# CARA_brain_v1_2.net
KiCad netlist of a schematic drawn in EAGLE
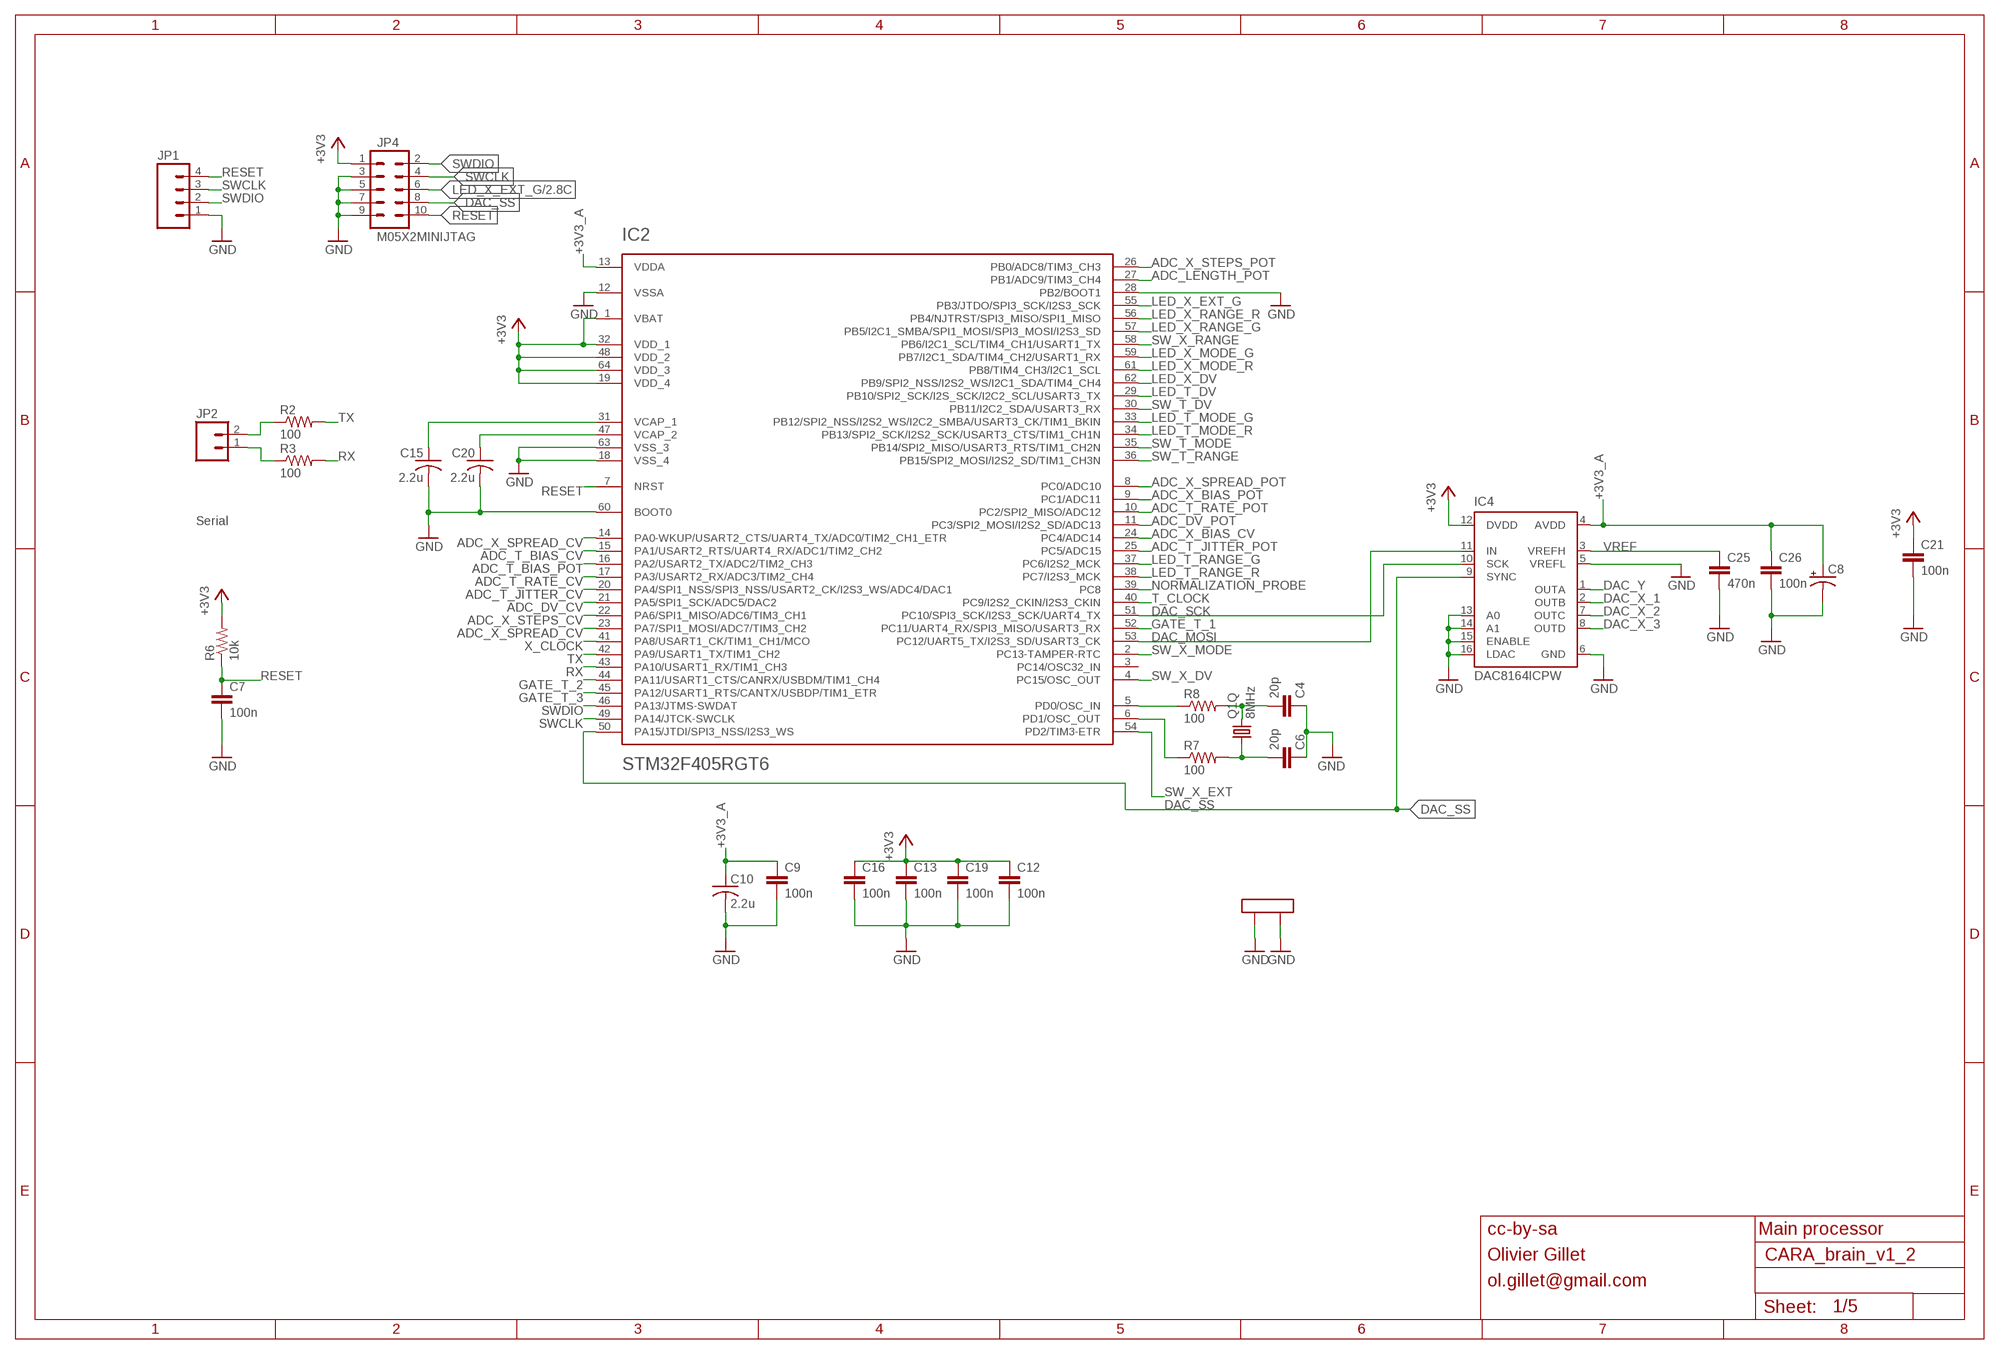
[diagram p0: schematic, sheet 1]
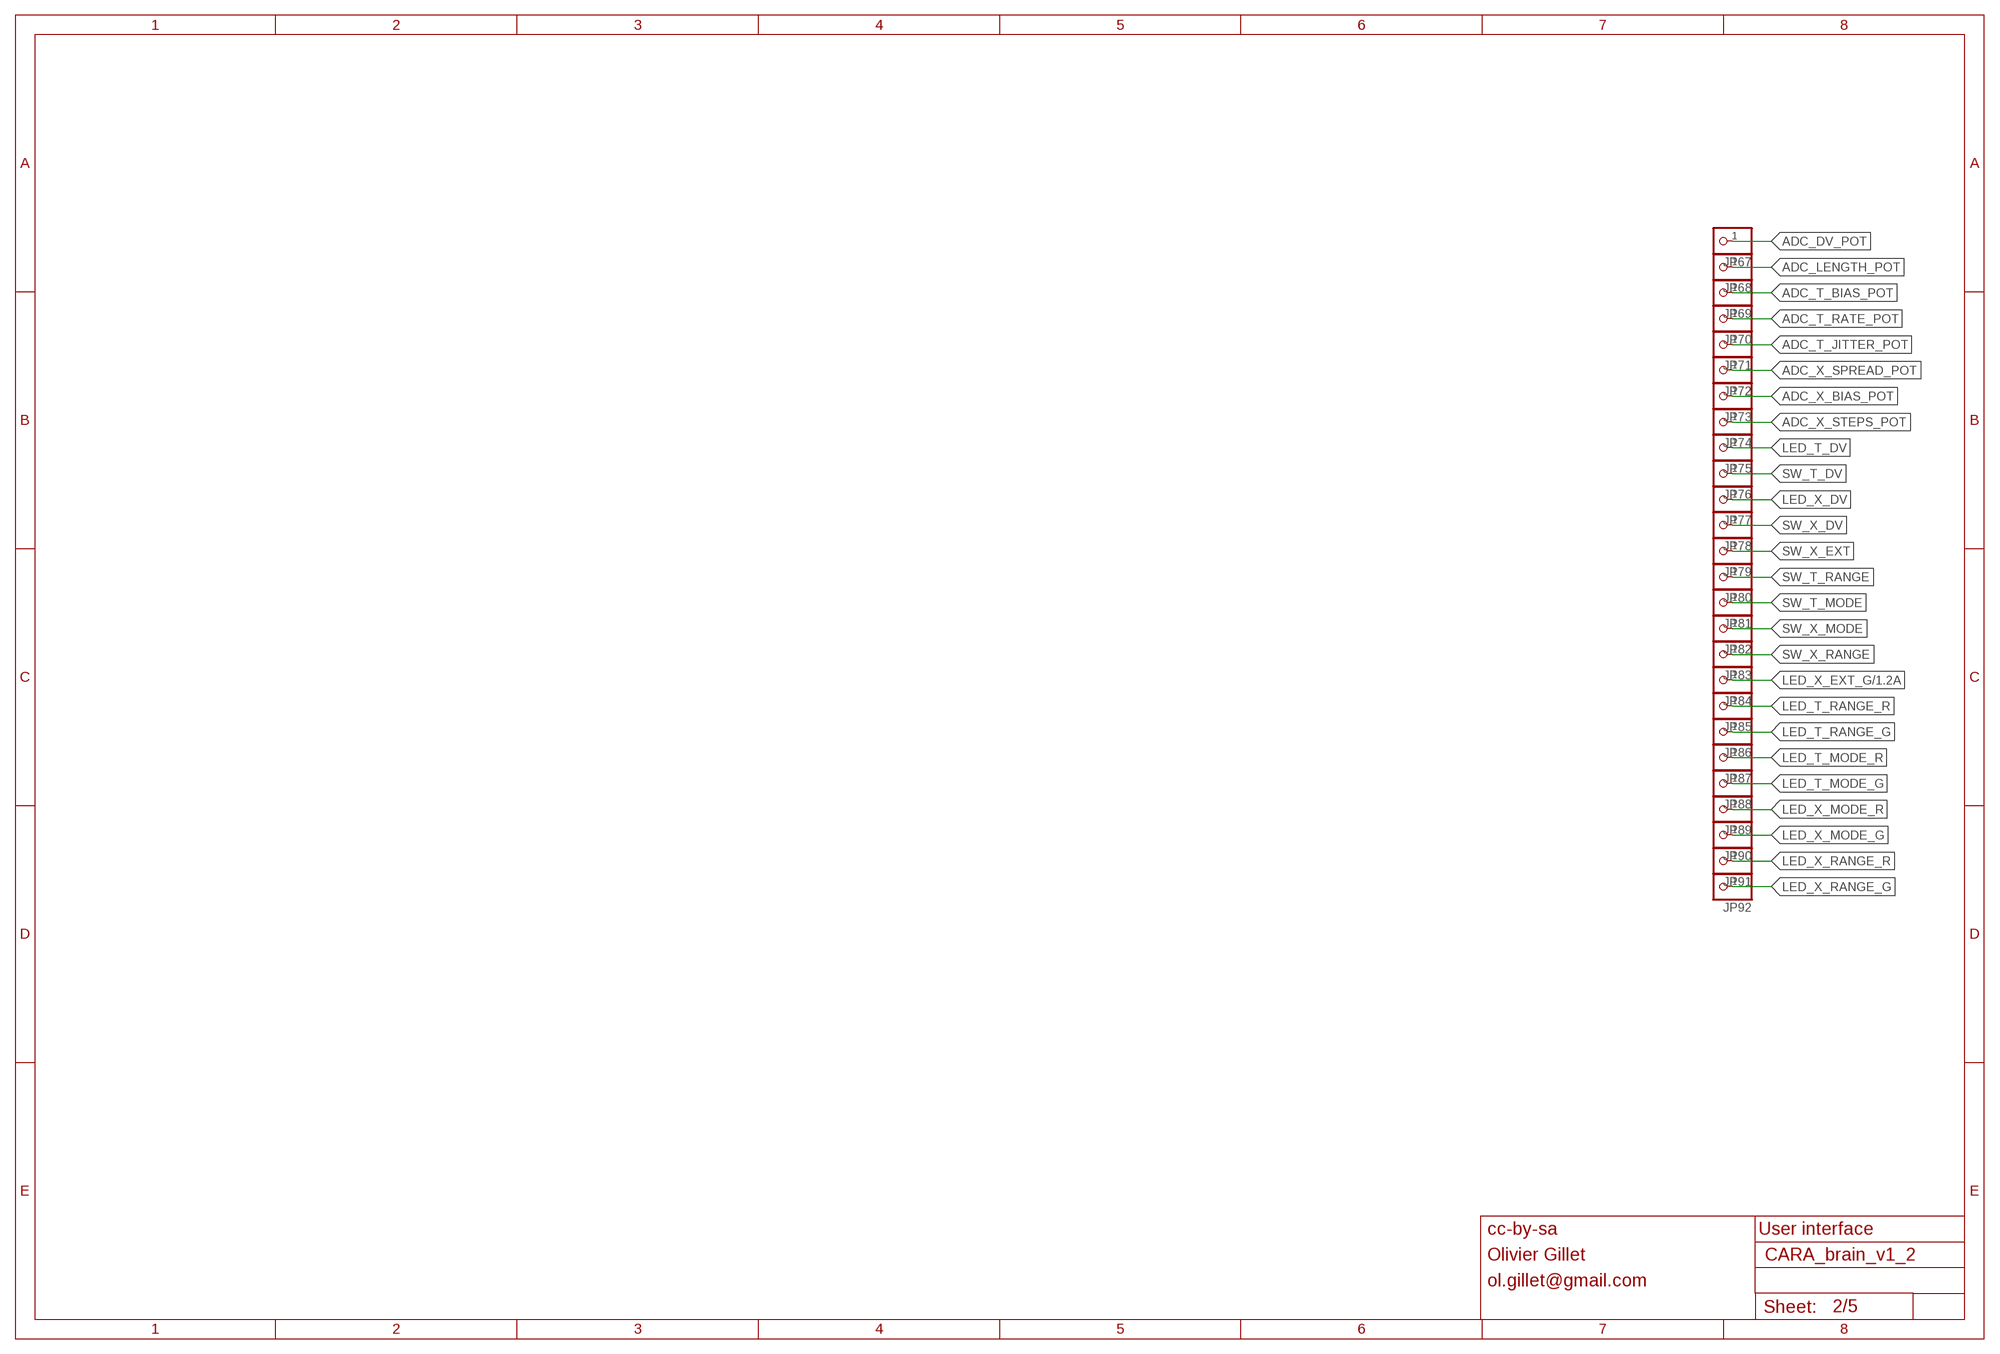
[diagram p1: schematic, sheet 2]
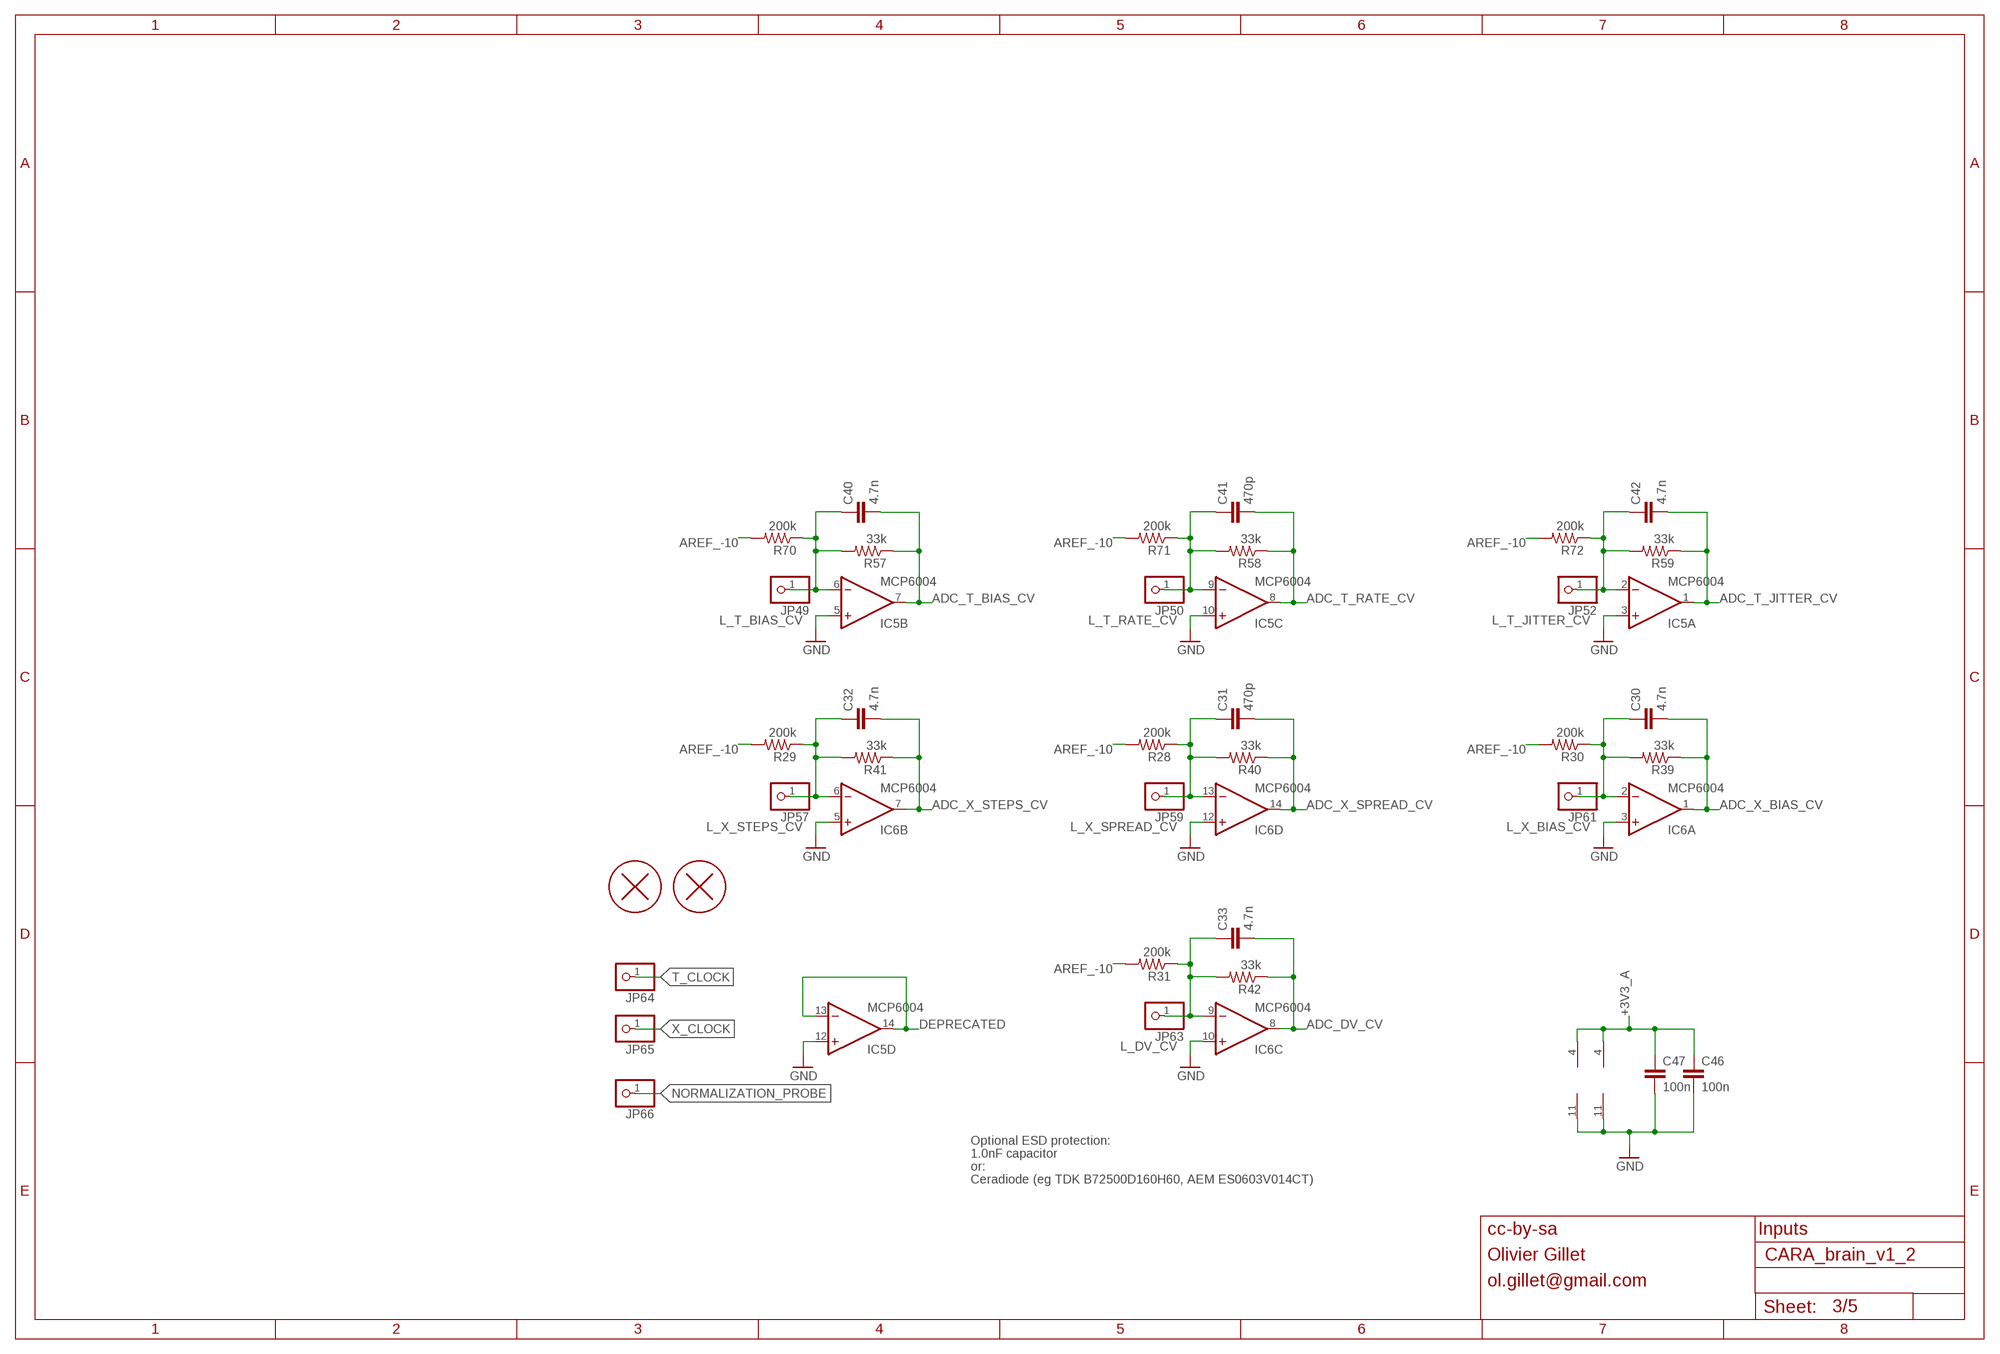
[diagram p2: schematic, sheet 3]
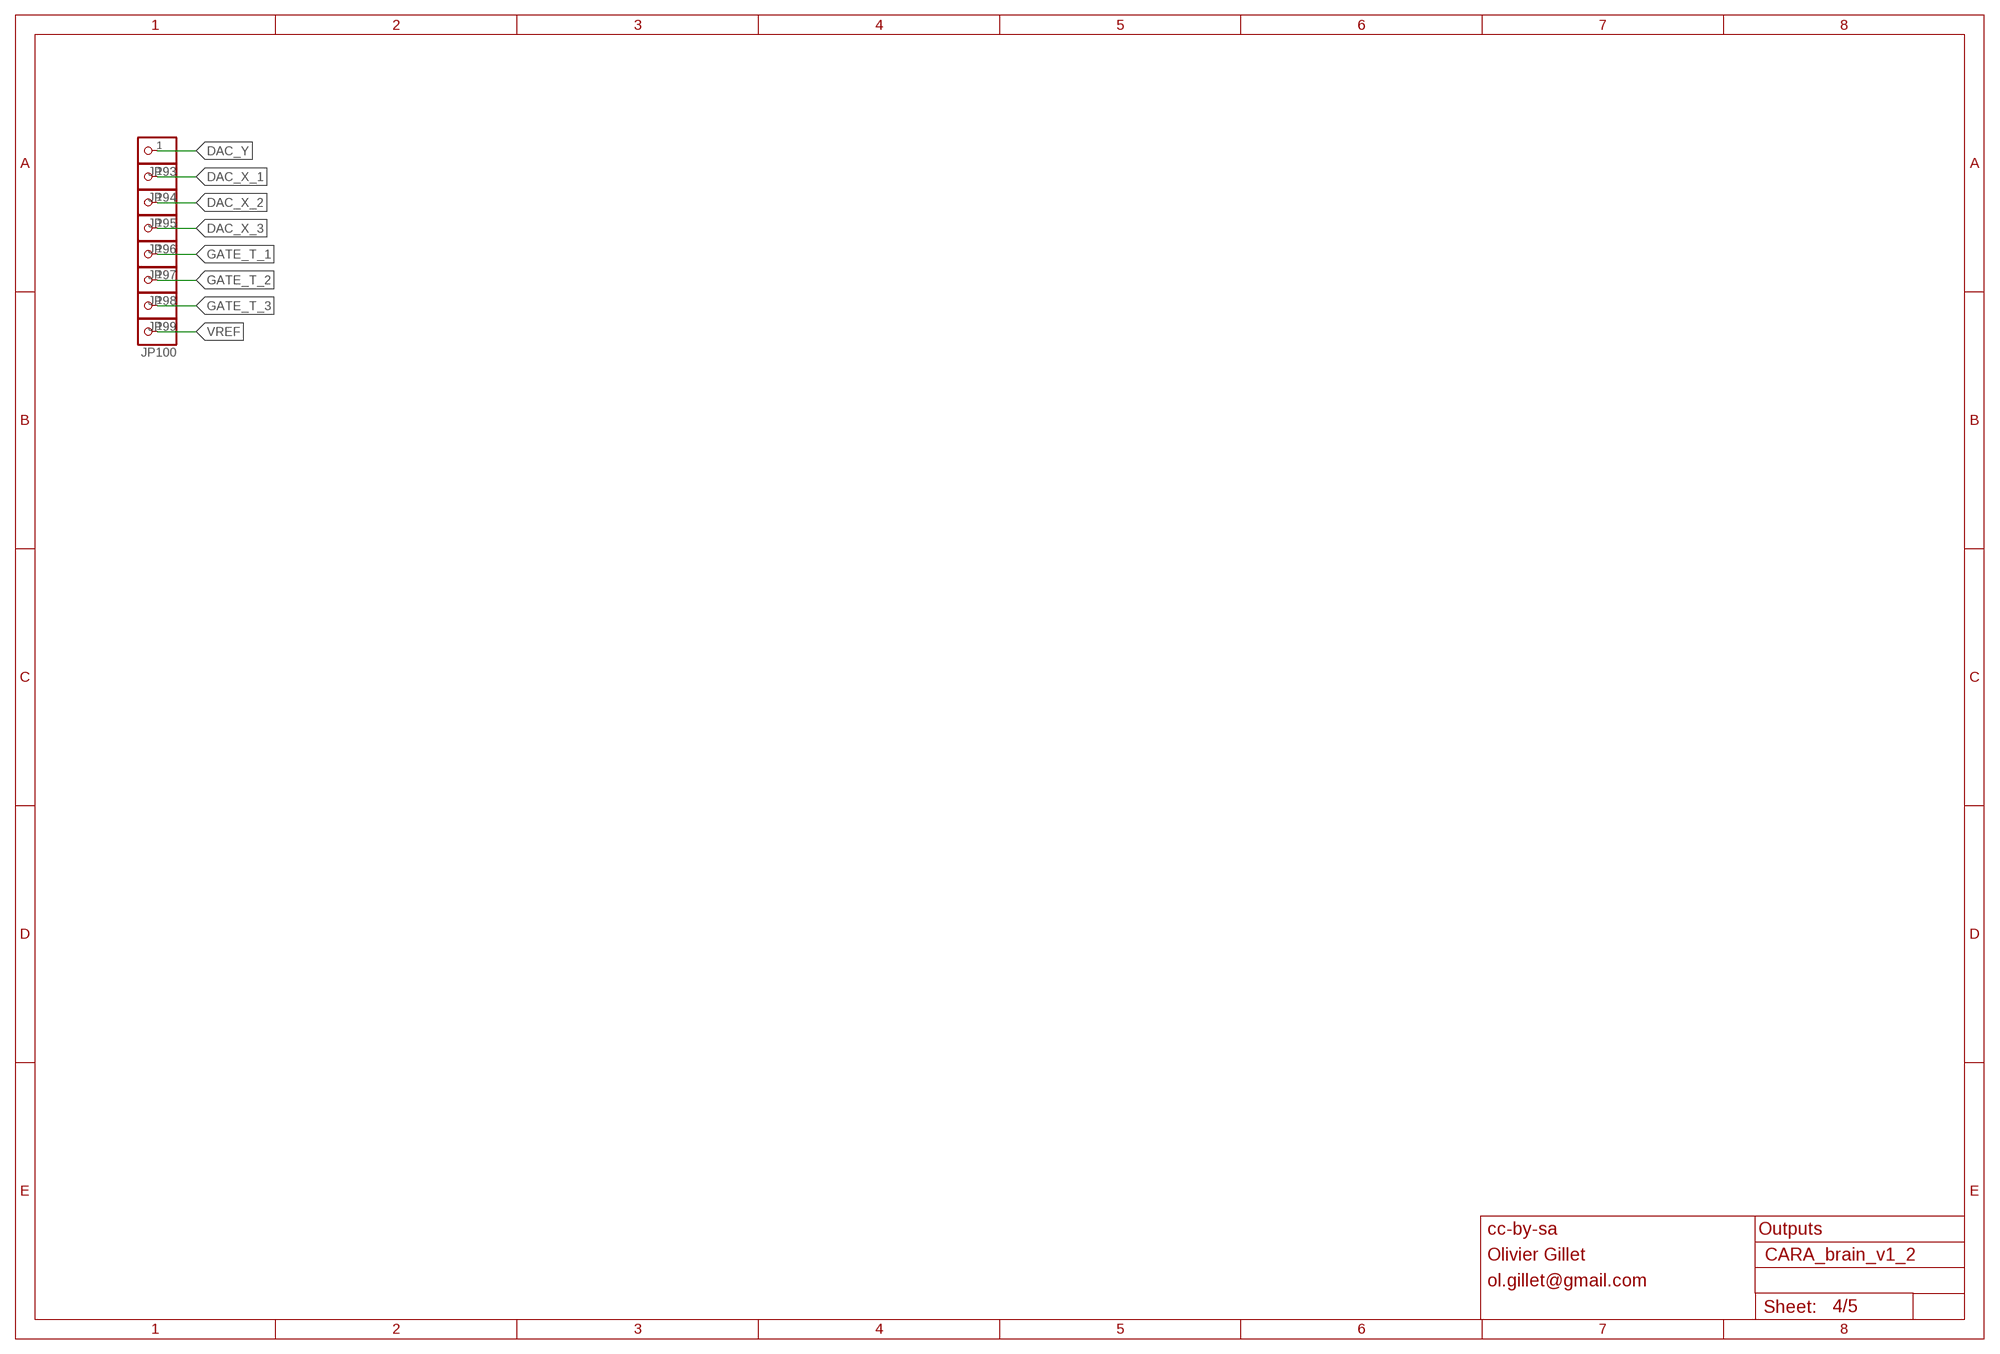
[diagram p3: schematic, sheet 4]
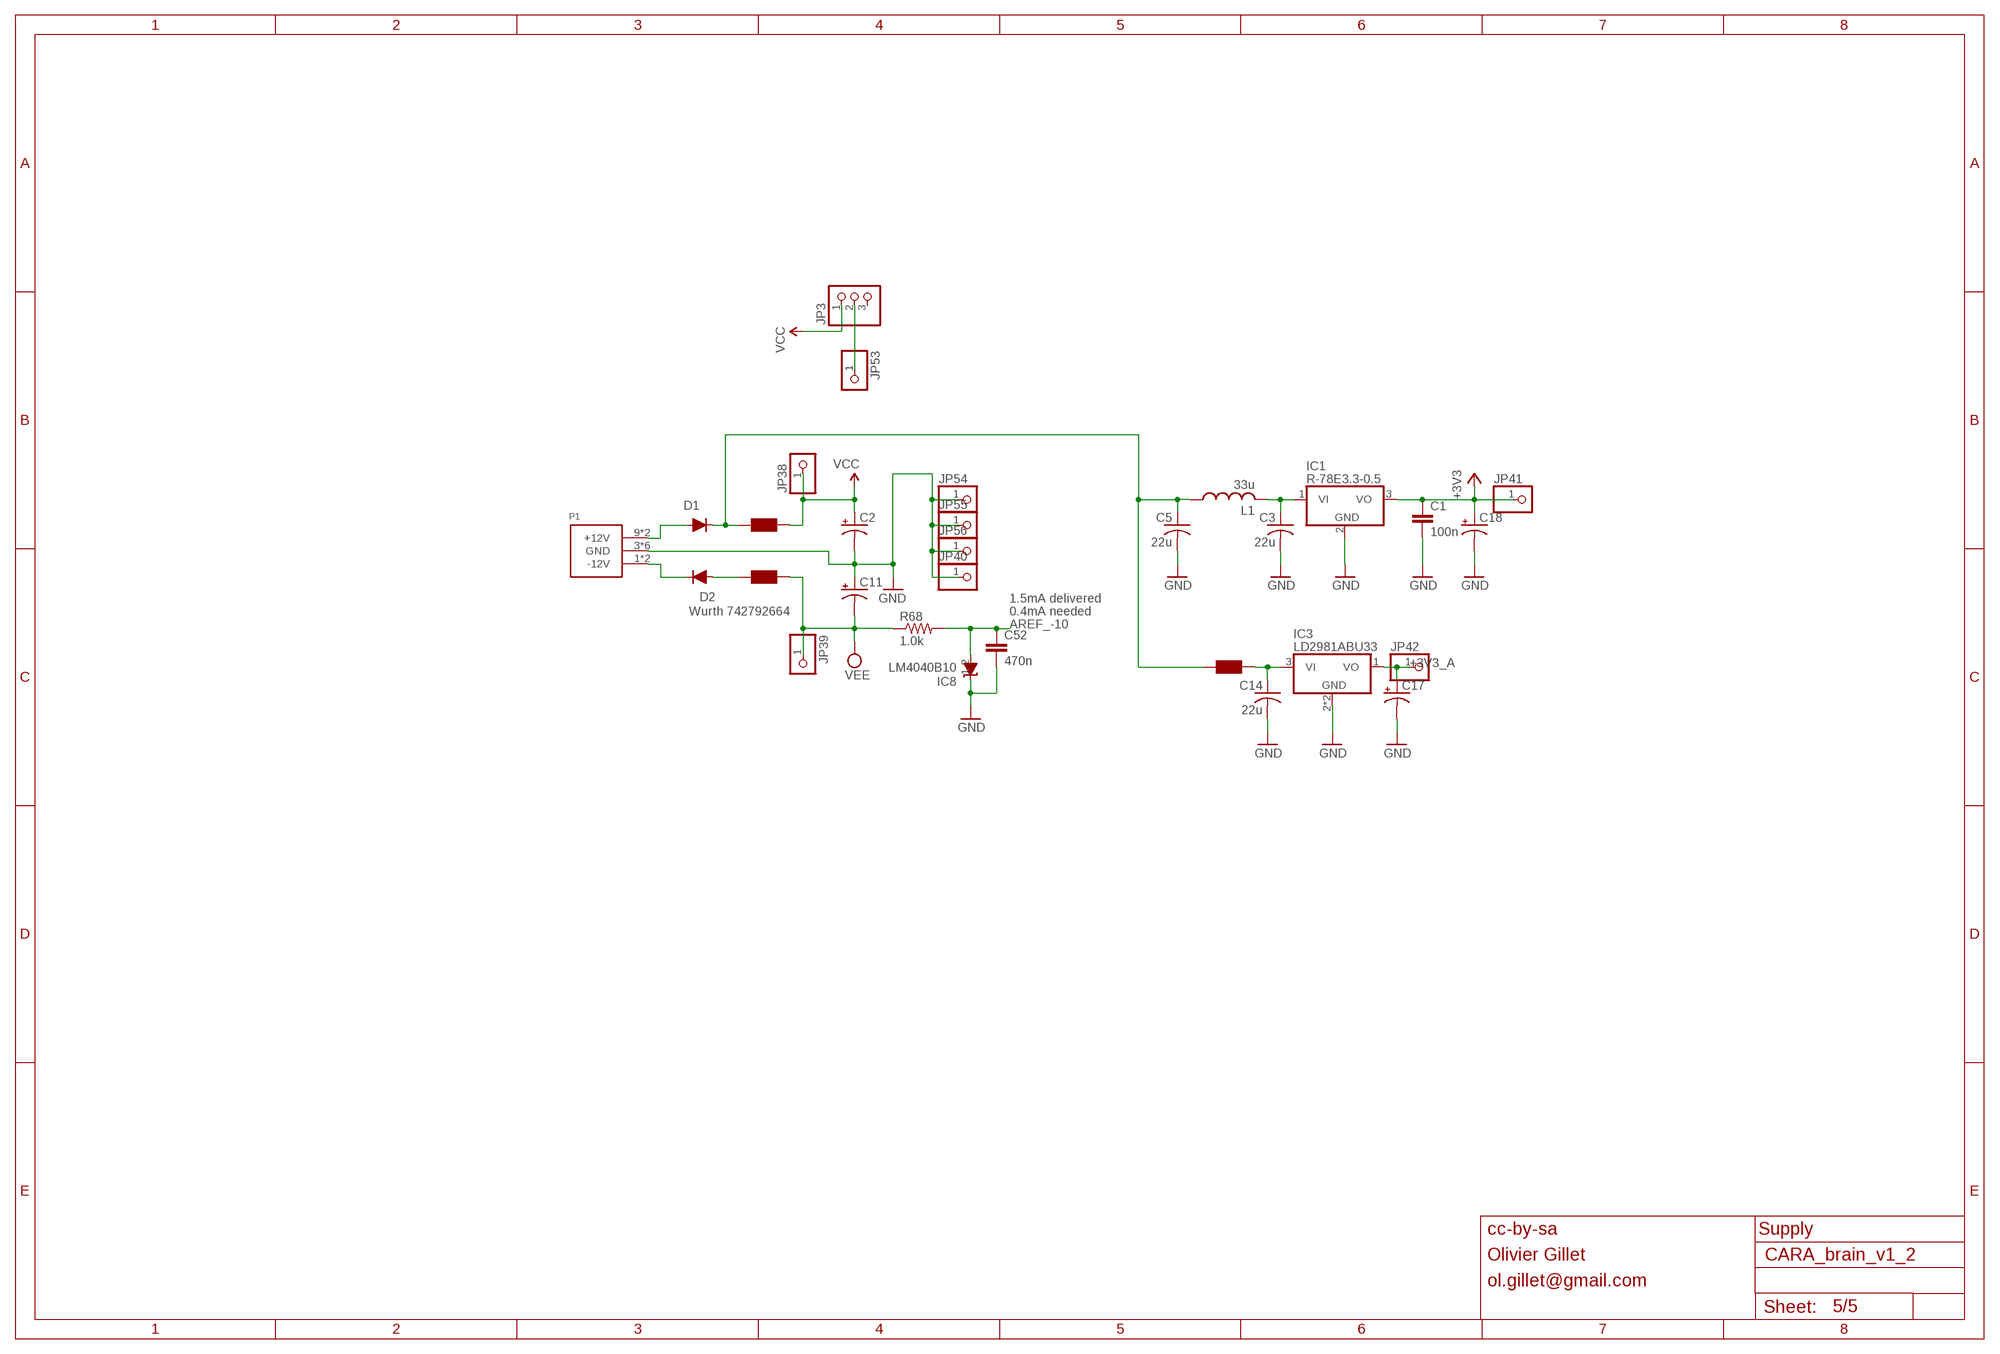
[diagram p4: schematic, sheet 5]

(export (version "E")
  (design (tool "Eeschema 10.0.6"))
  (components
    (comp (ref "C4")
      (value "20p")
      (footprint "eagle-import:RESISTOR_0603")
      (libsource (lib "eagle-import") (part "CAPACITOR"))
    )
    (comp (ref "C6")
      (value "20p")
      (footprint "eagle-import:RESISTOR_0603")
      (libsource (lib "eagle-import") (part "CAPACITOR"))
    )
    (comp (ref "C7")
      (value "100n")
      (footprint "eagle-import:RESISTOR_0603")
      (libsource (lib "eagle-import") (part "CAPACITOR"))
    )
    (comp (ref "C8")
      (value "CAP_POLC")
      (footprint "eagle-import:PANASONIC_C")
      (libsource (lib "eagle-import") (part "CAP_POLC"))
    )
    (comp (ref "C9")
      (value "100n")
      (footprint "eagle-import:RESISTOR_0603")
      (libsource (lib "eagle-import") (part "CAPACITOR"))
    )
    (comp (ref "C10")
      (value "2.2u")
      (footprint "eagle-import:C0805")
      (libsource (lib "eagle-import") (part "C-USC0805"))
    )
    (comp (ref "C12")
      (value "100n")
      (footprint "eagle-import:RESISTOR_0603")
      (libsource (lib "eagle-import") (part "CAPACITOR"))
    )
    (comp (ref "C13")
      (value "100n")
      (footprint "eagle-import:RESISTOR_0603")
      (libsource (lib "eagle-import") (part "CAPACITOR"))
    )
    (comp (ref "C15")
      (value "2.2u")
      (footprint "eagle-import:C0805")
      (libsource (lib "eagle-import") (part "C-USC0805"))
    )
    (comp (ref "C16")
      (value "100n")
      (footprint "eagle-import:RESISTOR_0603")
      (libsource (lib "eagle-import") (part "CAPACITOR"))
    )
    (comp (ref "C19")
      (value "100n")
      (footprint "eagle-import:RESISTOR_0603")
      (libsource (lib "eagle-import") (part "CAPACITOR"))
    )
    (comp (ref "C20")
      (value "2.2u")
      (footprint "eagle-import:C0805")
      (libsource (lib "eagle-import") (part "C-USC0805"))
    )
    (comp (ref "C21")
      (value "100n")
      (footprint "eagle-import:RESISTOR_0603")
      (libsource (lib "eagle-import") (part "CAPACITOR"))
    )
    (comp (ref "C25")
      (value "470n")
      (footprint "eagle-import:RESISTOR_0603")
      (libsource (lib "eagle-import") (part "CAPACITOR"))
    )
    (comp (ref "C26")
      (value "100n")
      (footprint "eagle-import:RESISTOR_0603")
      (libsource (lib "eagle-import") (part "CAPACITOR"))
    )
    (comp (ref "IC2")
      (value "STM32F405RGT6")
      (footprint "eagle-import:TQFP-10X10-64")
      (libsource (lib "eagle-import") (part "STM32F20X"))
    )
    (comp (ref "IC4")
      (value "DAC8164ICPW")
      (footprint "eagle-import:SOP65P640X110-16N")
      (libsource (lib "eagle-import") (part "DAC8564"))
    )
    (comp (ref "JP1")
      (value "M04PTH")
      (footprint "eagle-import:1X04")
      (libsource (lib "eagle-import") (part "M04PTH"))
    )
    (comp (ref "JP2")
      (value "M02PTH")
      (footprint "eagle-import:1X02")
      (libsource (lib "eagle-import") (part "M02PTH"))
    )
    (comp (ref "JP4")
      (value "M05X2MINIJTAG")
      (footprint "eagle-import:2X5-1.27")
      (libsource (lib "eagle-import") (part "M05X2MINIJTAG"))
    )
    (comp (ref "Q1")
      (value "8MHz")
      (footprint "eagle-import:CTS406")
      (libsource (lib "eagle-import") (part "CRYSTAL"))
    )
    (comp (ref "R2")
      (value "100")
      (footprint "eagle-import:RESISTOR_0603")
      (libsource (lib "eagle-import") (part "RESISTOR"))
    )
    (comp (ref "R3")
      (value "100")
      (footprint "eagle-import:RESISTOR_0603")
      (libsource (lib "eagle-import") (part "RESISTOR"))
    )
    (comp (ref "R6")
      (value "10k")
      (footprint "eagle-import:RESISTOR_0603")
      (libsource (lib "eagle-import") (part "RESISTOR"))
    )
    (comp (ref "R7")
      (value "100")
      (footprint "eagle-import:RESISTOR_0603")
      (libsource (lib "eagle-import") (part "RESISTOR"))
    )
    (comp (ref "R8")
      (value "100")
      (footprint "eagle-import:RESISTOR_0603")
      (libsource (lib "eagle-import") (part "RESISTOR"))
    )
    (comp (ref "JP67")
      (value "PINHD-1X1")
      (footprint "eagle-import:1X01")
      (libsource (lib "eagle-import") (part "PINHD-1X1"))
    )
    (comp (ref "JP68")
      (value "PINHD-1X1")
      (footprint "eagle-import:1X01")
      (libsource (lib "eagle-import") (part "PINHD-1X1"))
    )
    (comp (ref "JP69")
      (value "PINHD-1X1")
      (footprint "eagle-import:1X01")
      (libsource (lib "eagle-import") (part "PINHD-1X1"))
    )
    (comp (ref "JP70")
      (value "PINHD-1X1")
      (footprint "eagle-import:1X01")
      (libsource (lib "eagle-import") (part "PINHD-1X1"))
    )
    (comp (ref "JP71")
      (value "PINHD-1X1")
      (footprint "eagle-import:1X01")
      (libsource (lib "eagle-import") (part "PINHD-1X1"))
    )
    (comp (ref "JP72")
      (value "PINHD-1X1")
      (footprint "eagle-import:1X01")
      (libsource (lib "eagle-import") (part "PINHD-1X1"))
    )
    (comp (ref "JP73")
      (value "PINHD-1X1")
      (footprint "eagle-import:1X01")
      (libsource (lib "eagle-import") (part "PINHD-1X1"))
    )
    (comp (ref "JP74")
      (value "PINHD-1X1")
      (footprint "eagle-import:1X01")
      (libsource (lib "eagle-import") (part "PINHD-1X1"))
    )
    (comp (ref "JP75")
      (value "PINHD-1X1")
      (footprint "eagle-import:1X01")
      (libsource (lib "eagle-import") (part "PINHD-1X1"))
    )
    (comp (ref "JP76")
      (value "PINHD-1X1")
      (footprint "eagle-import:1X01")
      (libsource (lib "eagle-import") (part "PINHD-1X1"))
    )
    (comp (ref "JP77")
      (value "PINHD-1X1")
      (footprint "eagle-import:1X01")
      (libsource (lib "eagle-import") (part "PINHD-1X1"))
    )
    (comp (ref "JP78")
      (value "PINHD-1X1")
      (footprint "eagle-import:1X01")
      (libsource (lib "eagle-import") (part "PINHD-1X1"))
    )
    (comp (ref "JP79")
      (value "PINHD-1X1")
      (footprint "eagle-import:1X01")
      (libsource (lib "eagle-import") (part "PINHD-1X1"))
    )
    (comp (ref "JP80")
      (value "PINHD-1X1")
      (footprint "eagle-import:1X01")
      (libsource (lib "eagle-import") (part "PINHD-1X1"))
    )
    (comp (ref "JP81")
      (value "PINHD-1X1")
      (footprint "eagle-import:1X01")
      (libsource (lib "eagle-import") (part "PINHD-1X1"))
    )
    (comp (ref "JP82")
      (value "PINHD-1X1")
      (footprint "eagle-import:1X01")
      (libsource (lib "eagle-import") (part "PINHD-1X1"))
    )
    (comp (ref "JP83")
      (value "PINHD-1X1")
      (footprint "eagle-import:1X01")
      (libsource (lib "eagle-import") (part "PINHD-1X1"))
    )
    (comp (ref "JP84")
      (value "PINHD-1X1")
      (footprint "eagle-import:1X01")
      (libsource (lib "eagle-import") (part "PINHD-1X1"))
    )
    (comp (ref "JP85")
      (value "PINHD-1X1")
      (footprint "eagle-import:1X01")
      (libsource (lib "eagle-import") (part "PINHD-1X1"))
    )
    (comp (ref "JP86")
      (value "PINHD-1X1")
      (footprint "eagle-import:1X01")
      (libsource (lib "eagle-import") (part "PINHD-1X1"))
    )
    (comp (ref "JP87")
      (value "PINHD-1X1")
      (footprint "eagle-import:1X01")
      (libsource (lib "eagle-import") (part "PINHD-1X1"))
    )
    (comp (ref "JP88")
      (value "PINHD-1X1")
      (footprint "eagle-import:1X01")
      (libsource (lib "eagle-import") (part "PINHD-1X1"))
    )
    (comp (ref "JP89")
      (value "PINHD-1X1")
      (footprint "eagle-import:1X01")
      (libsource (lib "eagle-import") (part "PINHD-1X1"))
    )
    (comp (ref "JP90")
      (value "PINHD-1X1")
      (footprint "eagle-import:1X01")
      (libsource (lib "eagle-import") (part "PINHD-1X1"))
    )
    (comp (ref "JP91")
      (value "PINHD-1X1")
      (footprint "eagle-import:1X01")
      (libsource (lib "eagle-import") (part "PINHD-1X1"))
    )
    (comp (ref "JP92")
      (value "PINHD-1X1")
      (footprint "eagle-import:1X01")
      (libsource (lib "eagle-import") (part "PINHD-1X1"))
    )
    (comp (ref "C1")
      (value "100n")
      (footprint "eagle-import:RESISTOR_0603")
      (libsource (lib "eagle-import") (part "CAPACITOR"))
    )
    (comp (ref "C2")
      (value "CAP_POLC")
      (footprint "eagle-import:PANASONIC_C")
      (libsource (lib "eagle-import") (part "CAP_POLC"))
    )
    (comp (ref "C3")
      (value "22u")
      (footprint "eagle-import:C1206")
      (libsource (lib "eagle-import") (part "C-USC1206"))
    )
    (comp (ref "C5")
      (value "22u")
      (footprint "eagle-import:C1206")
      (libsource (lib "eagle-import") (part "C-USC1206"))
    )
    (comp (ref "C11")
      (value "CAP_POLC")
      (footprint "eagle-import:PANASONIC_C")
      (libsource (lib "eagle-import") (part "CAP_POLC"))
    )
    (comp (ref "C14")
      (value "22u")
      (footprint "eagle-import:C1206")
      (libsource (lib "eagle-import") (part "C-USC1206"))
    )
    (comp (ref "C17")
      (value "CAP_POLC")
      (footprint "eagle-import:PANASONIC_C")
      (libsource (lib "eagle-import") (part "CAP_POLC"))
    )
    (comp (ref "C18")
      (value "CAP_POLC")
      (footprint "eagle-import:PANASONIC_C")
      (libsource (lib "eagle-import") (part "CAP_POLC"))
    )
    (comp (ref "C52")
      (value "470n")
      (footprint "eagle-import:RESISTOR_0603")
      (libsource (lib "eagle-import") (part "CAPACITOR"))
    )
    (comp (ref "D1")
      (value "1N5819HW")
      (footprint "eagle-import:SOD123")
      (libsource (lib "eagle-import") (part "DIODE"))
    )
    (comp (ref "D2")
      (value "1N5819HW")
      (footprint "eagle-import:SOD123")
      (libsource (lib "eagle-import") (part "DIODE"))
    )
    (comp (ref "F1")
      (value "FERRITE-BEAD")
      (footprint "eagle-import:RESISTOR_0603")
      (libsource (lib "eagle-import") (part "FERRITE-BEAD"))
    )
    (comp (ref "F2")
      (value "FERRITE-BEAD")
      (footprint "eagle-import:RESISTOR_0603")
      (libsource (lib "eagle-import") (part "FERRITE-BEAD"))
    )
    (comp (ref "F3")
      (value "FERRITE-BEAD")
      (footprint "eagle-import:RESISTOR_0603")
      (libsource (lib "eagle-import") (part "FERRITE-BEAD"))
    )
    (comp (ref "IC1")
      (value "R-78E3.3-0.5")
      (footprint "eagle-import:WE78")
      (libsource (lib "eagle-import") (part "WE173950378"))
    )
    (comp (ref "IC3")
      (value "LD2981ABU33")
      (footprint "eagle-import:SOT89")
      (libsource (lib "eagle-import") (part "LD2981"))
    )
    (comp (ref "IC8")
      (value "LM4040B10")
      (footprint "eagle-import:SOT23")
      (libsource (lib "eagle-import") (part "LM4040SOT23"))
    )
    (comp (ref "JP3")
      (value "PINHD-1X3")
      (footprint "eagle-import:1X03")
      (libsource (lib "eagle-import") (part "PINHD-1X3"))
    )
    (comp (ref "JP38")
      (value "PINHD-1X1")
      (footprint "eagle-import:1X01")
      (libsource (lib "eagle-import") (part "PINHD-1X1"))
    )
    (comp (ref "JP39")
      (value "PINHD-1X1")
      (footprint "eagle-import:1X01")
      (libsource (lib "eagle-import") (part "PINHD-1X1"))
    )
    (comp (ref "JP40")
      (value "PINHD-1X1")
      (footprint "eagle-import:1X01")
      (libsource (lib "eagle-import") (part "PINHD-1X1"))
    )
    (comp (ref "JP41")
      (value "PINHD-1X1")
      (footprint "eagle-import:1X01")
      (libsource (lib "eagle-import") (part "PINHD-1X1"))
    )
    (comp (ref "JP42")
      (value "PINHD-1X1")
      (footprint "eagle-import:1X01")
      (libsource (lib "eagle-import") (part "PINHD-1X1"))
    )
    (comp (ref "JP53")
      (value "PINHD-1X1")
      (footprint "eagle-import:1X01")
      (libsource (lib "eagle-import") (part "PINHD-1X1"))
    )
    (comp (ref "JP54")
      (value "PINHD-1X1")
      (footprint "eagle-import:1X01")
      (libsource (lib "eagle-import") (part "PINHD-1X1"))
    )
    (comp (ref "JP55")
      (value "PINHD-1X1")
      (footprint "eagle-import:1X01")
      (libsource (lib "eagle-import") (part "PINHD-1X1"))
    )
    (comp (ref "JP56")
      (value "PINHD-1X1")
      (footprint "eagle-import:1X01")
      (libsource (lib "eagle-import") (part "PINHD-1X1"))
    )
    (comp (ref "L1")
      (value "33u")
      (footprint "eagle-import:L2012C")
      (libsource (lib "eagle-import") (part "L-USL2012C"))
    )
    (comp (ref "P1")
      (value "POWER_SIMPLE10")
      (footprint "eagle-import:POWER_10")
      (libsource (lib "eagle-import") (part "POWER_SIMPLE10"))
    )
    (comp (ref "R68")
      (value "1.0k")
      (footprint "eagle-import:RESISTOR_0603")
      (libsource (lib "eagle-import") (part "RESISTOR"))
    )
    (comp (ref "C30")
      (value "4.7n")
      (footprint "eagle-import:RESISTOR_0603")
      (libsource (lib "eagle-import") (part "CAPACITOR"))
    )
    (comp (ref "C31")
      (value "470p")
      (footprint "eagle-import:RESISTOR_0603")
      (libsource (lib "eagle-import") (part "CAPACITOR"))
    )
    (comp (ref "C32")
      (value "4.7n")
      (footprint "eagle-import:RESISTOR_0603")
      (libsource (lib "eagle-import") (part "CAPACITOR"))
    )
    (comp (ref "C33")
      (value "4.7n")
      (footprint "eagle-import:RESISTOR_0603")
      (libsource (lib "eagle-import") (part "CAPACITOR"))
    )
    (comp (ref "C40")
      (value "4.7n")
      (footprint "eagle-import:RESISTOR_0603")
      (libsource (lib "eagle-import") (part "CAPACITOR"))
    )
    (comp (ref "C41")
      (value "470p")
      (footprint "eagle-import:RESISTOR_0603")
      (libsource (lib "eagle-import") (part "CAPACITOR"))
    )
    (comp (ref "C42")
      (value "4.7n")
      (footprint "eagle-import:RESISTOR_0603")
      (libsource (lib "eagle-import") (part "CAPACITOR"))
    )
    (comp (ref "C46")
      (value "100n")
      (footprint "eagle-import:RESISTOR_0603")
      (libsource (lib "eagle-import") (part "CAPACITOR"))
    )
    (comp (ref "C47")
      (value "100n")
      (footprint "eagle-import:RESISTOR_0603")
      (libsource (lib "eagle-import") (part "CAPACITOR"))
    )
    (comp (ref "H1")
      (value "PCB_SCREW")
      (footprint "eagle-import:PCB_SCREW")
      (libsource (lib "eagle-import") (part "PCB_SCREW"))
    )
    (comp (ref "H2")
      (value "PCB_SCREW")
      (footprint "eagle-import:PCB_SCREW")
      (libsource (lib "eagle-import") (part "PCB_SCREW"))
    )
    (comp (ref "IC5")
      (value "MCP6004")
      (footprint "eagle-import:TSSOP14_065")
      (libsource (lib "eagle-import") (part "TL074PW"))
    )
    (comp (ref "IC6")
      (value "MCP6004")
      (footprint "eagle-import:TSSOP14_065")
      (libsource (lib "eagle-import") (part "TL074PW"))
    )
    (comp (ref "JP49")
      (value "PINHD-1X1")
      (footprint "eagle-import:1X01")
      (libsource (lib "eagle-import") (part "PINHD-1X1"))
    )
    (comp (ref "JP50")
      (value "PINHD-1X1")
      (footprint "eagle-import:1X01")
      (libsource (lib "eagle-import") (part "PINHD-1X1"))
    )
    (comp (ref "JP52")
      (value "PINHD-1X1")
      (footprint "eagle-import:1X01")
      (libsource (lib "eagle-import") (part "PINHD-1X1"))
    )
    (comp (ref "JP57")
      (value "PINHD-1X1")
      (footprint "eagle-import:1X01")
      (libsource (lib "eagle-import") (part "PINHD-1X1"))
    )
    (comp (ref "JP59")
      (value "PINHD-1X1")
      (footprint "eagle-import:1X01")
      (libsource (lib "eagle-import") (part "PINHD-1X1"))
    )
    (comp (ref "JP61")
      (value "PINHD-1X1")
      (footprint "eagle-import:1X01")
      (libsource (lib "eagle-import") (part "PINHD-1X1"))
    )
    (comp (ref "JP63")
      (value "PINHD-1X1")
      (footprint "eagle-import:1X01")
      (libsource (lib "eagle-import") (part "PINHD-1X1"))
    )
    (comp (ref "JP64")
      (value "PINHD-1X1")
      (footprint "eagle-import:1X01")
      (libsource (lib "eagle-import") (part "PINHD-1X1"))
    )
    (comp (ref "JP65")
      (value "PINHD-1X1")
      (footprint "eagle-import:1X01")
      (libsource (lib "eagle-import") (part "PINHD-1X1"))
    )
    (comp (ref "JP66")
      (value "PINHD-1X1")
      (footprint "eagle-import:1X01")
      (libsource (lib "eagle-import") (part "PINHD-1X1"))
    )
    (comp (ref "R28")
      (value "200k")
      (footprint "eagle-import:RESISTOR_0603")
      (libsource (lib "eagle-import") (part "RESISTOR"))
    )
    (comp (ref "R29")
      (value "200k")
      (footprint "eagle-import:RESISTOR_0603")
      (libsource (lib "eagle-import") (part "RESISTOR"))
    )
    (comp (ref "R30")
      (value "200k")
      (footprint "eagle-import:RESISTOR_0603")
      (libsource (lib "eagle-import") (part "RESISTOR"))
    )
    (comp (ref "R31")
      (value "200k")
      (footprint "eagle-import:RESISTOR_0603")
      (libsource (lib "eagle-import") (part "RESISTOR"))
    )
    (comp (ref "R39")
      (value "33k")
      (footprint "eagle-import:RESISTOR_0603")
      (libsource (lib "eagle-import") (part "RESISTOR"))
    )
    (comp (ref "R40")
      (value "33k")
      (footprint "eagle-import:RESISTOR_0603")
      (libsource (lib "eagle-import") (part "RESISTOR"))
    )
    (comp (ref "R41")
      (value "33k")
      (footprint "eagle-import:RESISTOR_0603")
      (libsource (lib "eagle-import") (part "RESISTOR"))
    )
    (comp (ref "R42")
      (value "33k")
      (footprint "eagle-import:RESISTOR_0603")
      (libsource (lib "eagle-import") (part "RESISTOR"))
    )
    (comp (ref "R57")
      (value "33k")
      (footprint "eagle-import:RESISTOR_0603")
      (libsource (lib "eagle-import") (part "RESISTOR"))
    )
    (comp (ref "R58")
      (value "33k")
      (footprint "eagle-import:RESISTOR_0603")
      (libsource (lib "eagle-import") (part "RESISTOR"))
    )
    (comp (ref "R59")
      (value "33k")
      (footprint "eagle-import:RESISTOR_0603")
      (libsource (lib "eagle-import") (part "RESISTOR"))
    )
    (comp (ref "R70")
      (value "200k")
      (footprint "eagle-import:RESISTOR_0603")
      (libsource (lib "eagle-import") (part "RESISTOR"))
    )
    (comp (ref "R71")
      (value "200k")
      (footprint "eagle-import:RESISTOR_0603")
      (libsource (lib "eagle-import") (part "RESISTOR"))
    )
    (comp (ref "R72")
      (value "200k")
      (footprint "eagle-import:RESISTOR_0603")
      (libsource (lib "eagle-import") (part "RESISTOR"))
    )
    (comp (ref "JP93")
      (value "PINHD-1X1")
      (footprint "eagle-import:1X01")
      (libsource (lib "eagle-import") (part "PINHD-1X1"))
    )
    (comp (ref "JP94")
      (value "PINHD-1X1")
      (footprint "eagle-import:1X01")
      (libsource (lib "eagle-import") (part "PINHD-1X1"))
    )
    (comp (ref "JP95")
      (value "PINHD-1X1")
      (footprint "eagle-import:1X01")
      (libsource (lib "eagle-import") (part "PINHD-1X1"))
    )
    (comp (ref "JP96")
      (value "PINHD-1X1")
      (footprint "eagle-import:1X01")
      (libsource (lib "eagle-import") (part "PINHD-1X1"))
    )
    (comp (ref "JP97")
      (value "PINHD-1X1")
      (footprint "eagle-import:1X01")
      (libsource (lib "eagle-import") (part "PINHD-1X1"))
    )
    (comp (ref "JP98")
      (value "PINHD-1X1")
      (footprint "eagle-import:1X01")
      (libsource (lib "eagle-import") (part "PINHD-1X1"))
    )
    (comp (ref "JP99")
      (value "PINHD-1X1")
      (footprint "eagle-import:1X01")
      (libsource (lib "eagle-import") (part "PINHD-1X1"))
    )
    (comp (ref "JP100")
      (value "PINHD-1X1")
      (footprint "eagle-import:1X01")
      (libsource (lib "eagle-import") (part "PINHD-1X1"))
    )
  )
  (nets
    (net (code "1") (name "+3V3") (class "Default")
      (node (ref "C1") (pin "1") (pinfunction "1_1") (pintype "passive"))
      (node (ref "C12") (pin "1") (pinfunction "1_1") (pintype "passive"))
      (node (ref "C13") (pin "1") (pinfunction "1_1") (pintype "passive"))
      (node (ref "C16") (pin "1") (pinfunction "1_1") (pintype "passive"))
      (node (ref "C18") (pin "+") (pinfunction "+_+") (pintype "passive"))
      (node (ref "C19") (pin "1") (pinfunction "1_1") (pintype "passive"))
      (node (ref "C21") (pin "1") (pinfunction "1_1") (pintype "passive"))
      (node (ref "IC1") (pin "3") (pinfunction "VO_3") (pintype "passive"))
      (node (ref "IC2") (pin "1") (pinfunction "VBAT_1") (pintype "power_in"))
      (node (ref "IC2") (pin "19") (pinfunction "VDD_4_19") (pintype "power_in"))
      (node (ref "IC2") (pin "32") (pinfunction "VDD_1_32") (pintype "power_in"))
      (node (ref "IC2") (pin "48") (pinfunction "VDD_2_48") (pintype "power_in"))
      (node (ref "IC2") (pin "64") (pinfunction "VDD_3_64") (pintype "power_in"))
      (node (ref "IC4") (pin "12") (pinfunction "DVDD_12") (pintype "power_in"))
      (node (ref "JP4") (pin "1") (pinfunction "1_1") (pintype "passive"))
      (node (ref "JP41") (pin "1") (pinfunction "1_1") (pintype "passive"))
      (node (ref "R6") (pin "2") (pinfunction "2_2") (pintype "passive"))
    )
    (net (code "2") (name "+3V3_A") (class "Default")
      (node (ref "C10") (pin "1") (pinfunction "1_1") (pintype "passive"))
      (node (ref "C17") (pin "+") (pinfunction "+_+") (pintype "passive"))
      (node (ref "C26") (pin "1") (pinfunction "1_1") (pintype "passive"))
      (node (ref "C46") (pin "1") (pinfunction "1_1") (pintype "passive"))
      (node (ref "C47") (pin "1") (pinfunction "1_1") (pintype "passive"))
      (node (ref "C8") (pin "+") (pinfunction "+_+") (pintype "passive"))
      (node (ref "C9") (pin "1") (pinfunction "1_1") (pintype "passive"))
      (node (ref "IC2") (pin "13") (pinfunction "VDDA_13") (pintype "power_in"))
      (node (ref "IC3") (pin "1") (pinfunction "VO_1") (pintype "passive"))
      (node (ref "IC4") (pin "4") (pinfunction "AVDD_4") (pintype "power_in"))
      (node (ref "IC5") (pin "4") (pinfunction "V+_4") (pintype "power_in"))
      (node (ref "IC6") (pin "4") (pinfunction "V+_4") (pintype "power_in"))
      (node (ref "JP42") (pin "1") (pinfunction "1_1") (pintype "passive"))
    )
    (net (code "3") (name "ADC_DV_CV") (class "Default")
      (node (ref "C33") (pin "2") (pinfunction "2_2") (pintype "passive"))
      (node (ref "IC2") (pin "21") (pinfunction "PA5/SPI1_SCK/ADC5/DAC2_21") (pintype "bidirectional"))
      (node (ref "IC6") (pin "8") (pinfunction "OUT_8") (pintype "output"))
      (node (ref "R42") (pin "1") (pinfunction "1_1") (pintype "passive"))
    )
    (net (code "4") (name "ADC_DV_POT") (class "Default")
      (node (ref "IC2") (pin "11") (pinfunction "PC3/SPI2_MOSI/I2S2_SD/ADC13_11") (pintype "bidirectional"))
      (node (ref "JP67") (pin "1") (pinfunction "1_1") (pintype "passive"))
    )
    (net (code "5") (name "ADC_LENGTH_POT") (class "Default")
      (node (ref "IC2") (pin "27") (pinfunction "PB1/ADC9/TIM3_CH4_27") (pintype "bidirectional"))
      (node (ref "JP68") (pin "1") (pinfunction "1_1") (pintype "passive"))
    )
    (net (code "6") (name "ADC_T_BIAS_CV") (class "Default")
      (node (ref "C40") (pin "2") (pinfunction "2_2") (pintype "passive"))
      (node (ref "IC2") (pin "15") (pinfunction "PA1/USART2_RTS/UART4_RX/ADC1/TIM2_CH2_15") (pintype "bidirectional"))
      (node (ref "IC5") (pin "7") (pinfunction "OUT_7") (pintype "output"))
      (node (ref "R57") (pin "1") (pinfunction "1_1") (pintype "passive"))
    )
    (net (code "7") (name "ADC_T_BIAS_POT") (class "Default")
      (node (ref "IC2") (pin "16") (pinfunction "PA2/USART2_TX/ADC2/TIM2_CH3_16") (pintype "bidirectional"))
      (node (ref "JP69") (pin "1") (pinfunction "1_1") (pintype "passive"))
    )
    (net (code "8") (name "ADC_T_JITTER_CV") (class "Default")
      (node (ref "C42") (pin "2") (pinfunction "2_2") (pintype "passive"))
      (node (ref "IC2") (pin "20") (pinfunction "PA4/SPI1_NSS/SPI3_NSS/USART2_CK/I2S3_WS/ADC4/DAC1_20") (pintype "bidirectional"))
      (node (ref "IC5") (pin "1") (pinfunction "OUT_1") (pintype "output"))
      (node (ref "R59") (pin "1") (pinfunction "1_1") (pintype "passive"))
    )
    (net (code "9") (name "ADC_T_JITTER_POT") (class "Default")
      (node (ref "IC2") (pin "25") (pinfunction "PC5/ADC15_25") (pintype "bidirectional"))
      (node (ref "JP71") (pin "1") (pinfunction "1_1") (pintype "passive"))
    )
    (net (code "10") (name "ADC_T_RATE_CV") (class "Default")
      (node (ref "C41") (pin "2") (pinfunction "2_2") (pintype "passive"))
      (node (ref "IC2") (pin "17") (pinfunction "PA3/USART2_RX/ADC3/TIM2_CH4_17") (pintype "bidirectional"))
      (node (ref "IC5") (pin "8") (pinfunction "OUT_8") (pintype "output"))
      (node (ref "R58") (pin "1") (pinfunction "1_1") (pintype "passive"))
    )
    (net (code "11") (name "ADC_T_RATE_POT") (class "Default")
      (node (ref "IC2") (pin "10") (pinfunction "PC2/SPI2_MISO/ADC12_10") (pintype "bidirectional"))
      (node (ref "JP70") (pin "1") (pinfunction "1_1") (pintype "passive"))
    )
    (net (code "12") (name "ADC_X_BIAS_CV") (class "Default")
      (node (ref "C30") (pin "2") (pinfunction "2_2") (pintype "passive"))
      (node (ref "IC2") (pin "24") (pinfunction "PC4/ADC14_24") (pintype "bidirectional"))
      (node (ref "IC6") (pin "1") (pinfunction "OUT_1") (pintype "output"))
      (node (ref "R39") (pin "1") (pinfunction "1_1") (pintype "passive"))
    )
    (net (code "13") (name "ADC_X_BIAS_POT") (class "Default")
      (node (ref "IC2") (pin "9") (pinfunction "PC1/ADC11_9") (pintype "bidirectional"))
      (node (ref "JP73") (pin "1") (pinfunction "1_1") (pintype "passive"))
    )
    (net (code "14") (name "ADC_X_SPREAD_CV") (class "Default")
      (node (ref "C31") (pin "2") (pinfunction "2_2") (pintype "passive"))
      (node (ref "IC2") (pin "14") (pinfunction "PA0-WKUP/USART2_CTS/UART4_TX/ADC0/TIM2_CH1_ETR_14") (pintype "bidirectional"))
      (node (ref "IC2") (pin "23") (pinfunction "PA7/SPI1_MOSI/ADC7/TIM3_CH2_23") (pintype "bidirectional"))
      (node (ref "IC6") (pin "14") (pinfunction "OUT_14") (pintype "output"))
      (node (ref "R40") (pin "1") (pinfunction "1_1") (pintype "passive"))
    )
    (net (code "15") (name "ADC_X_SPREAD_POT") (class "Default")
      (node (ref "IC2") (pin "8") (pinfunction "PC0/ADC10_8") (pintype "bidirectional"))
      (node (ref "JP72") (pin "1") (pinfunction "1_1") (pintype "passive"))
    )
    (net (code "16") (name "ADC_X_STEPS_CV") (class "Default")
      (node (ref "C32") (pin "2") (pinfunction "2_2") (pintype "passive"))
      (node (ref "IC2") (pin "22") (pinfunction "PA6/SPI1_MISO/ADC6/TIM3_CH1_22") (pintype "bidirectional"))
      (node (ref "IC6") (pin "7") (pinfunction "OUT_7") (pintype "output"))
      (node (ref "R41") (pin "1") (pinfunction "1_1") (pintype "passive"))
    )
    (net (code "17") (name "ADC_X_STEPS_POT") (class "Default")
      (node (ref "IC2") (pin "26") (pinfunction "PB0/ADC8/TIM3_CH3_26") (pintype "bidirectional"))
      (node (ref "JP74") (pin "1") (pinfunction "1_1") (pintype "passive"))
    )
    (net (code "18") (name "AREF_-10") (class "Default")
      (node (ref "C52") (pin "1") (pinfunction "1_1") (pintype "passive"))
      (node (ref "IC8") (pin "2") (pinfunction "A_2") (pintype "passive"))
      (node (ref "R28") (pin "2") (pinfunction "2_2") (pintype "passive"))
      (node (ref "R29") (pin "2") (pinfunction "2_2") (pintype "passive"))
      (node (ref "R30") (pin "2") (pinfunction "2_2") (pintype "passive"))
      (node (ref "R31") (pin "2") (pinfunction "2_2") (pintype "passive"))
      (node (ref "R68") (pin "2") (pinfunction "2_2") (pintype "passive"))
      (node (ref "R70") (pin "2") (pinfunction "2_2") (pintype "passive"))
      (node (ref "R71") (pin "2") (pinfunction "2_2") (pintype "passive"))
      (node (ref "R72") (pin "2") (pinfunction "2_2") (pintype "passive"))
    )
    (net (code "19") (name "DAC_MOSI") (class "Default")
      (node (ref "IC2") (pin "53") (pinfunction "PC12/UART5_TX/I2S3_SD/USART3_CK_53") (pintype "bidirectional"))
      (node (ref "IC4") (pin "11") (pinfunction "IN_11") (pintype "input"))
    )
    (net (code "20") (name "DAC_SCK") (class "Default")
      (node (ref "IC2") (pin "51") (pinfunction "PC10/SPI3_SCK/I2S3_SCK/UART4_TX_51") (pintype "bidirectional"))
      (node (ref "IC4") (pin "10") (pinfunction "SCK_10") (pintype "input"))
    )
    (net (code "21") (name "DAC_SS") (class "Default")
      (node (ref "IC2") (pin "50") (pinfunction "PA15/JTDI/SPI3_NSS/I2S3_WS_50") (pintype "bidirectional"))
      (node (ref "IC4") (pin "9") (pinfunction "SYNC_9") (pintype "input"))
      (node (ref "JP4") (pin "8") (pinfunction "8_8") (pintype "passive"))
    )
    (net (code "22") (name "DAC_X_1") (class "Default")
      (node (ref "IC4") (pin "2") (pinfunction "OUTB_2") (pintype "output"))
      (node (ref "JP94") (pin "1") (pinfunction "1_1") (pintype "passive"))
    )
    (net (code "23") (name "DAC_X_2") (class "Default")
      (node (ref "IC4") (pin "7") (pinfunction "OUTC_7") (pintype "output"))
      (node (ref "JP95") (pin "1") (pinfunction "1_1") (pintype "passive"))
    )
    (net (code "24") (name "DAC_X_3") (class "Default")
      (node (ref "IC4") (pin "8") (pinfunction "OUTD_8") (pintype "output"))
      (node (ref "JP96") (pin "1") (pinfunction "1_1") (pintype "passive"))
    )
    (net (code "25") (name "DAC_Y") (class "Default")
      (node (ref "IC4") (pin "1") (pinfunction "OUTA_1") (pintype "output"))
      (node (ref "JP93") (pin "1") (pinfunction "1_1") (pintype "passive"))
    )
    (net (code "26") (name "DEPRECATED") (class "Default")
      (node (ref "IC5") (pin "13") (pinfunction "-IN_13") (pintype "input"))
      (node (ref "IC5") (pin "14") (pinfunction "OUT_14") (pintype "output"))
    )
    (net (code "27") (name "GATE_T_1") (class "Default")
      (node (ref "IC2") (pin "52") (pinfunction "PC11/UART4_RX/SPI3_MISO/USART3_RX_52") (pintype "bidirectional"))
      (node (ref "JP97") (pin "1") (pinfunction "1_1") (pintype "passive"))
    )
    (net (code "28") (name "GATE_T_2") (class "Default")
      (node (ref "IC2") (pin "44") (pinfunction "PA11/USART1_CTS/CANRX/USBDM/TIM1_CH4_44") (pintype "bidirectional"))
      (node (ref "JP98") (pin "1") (pinfunction "1_1") (pintype "passive"))
    )
    (net (code "29") (name "GATE_T_3") (class "Default")
      (node (ref "IC2") (pin "45") (pinfunction "PA12/USART1_RTS/CANTX/USBDP/TIM1_ETR_45") (pintype "bidirectional"))
      (node (ref "JP99") (pin "1") (pinfunction "1_1") (pintype "passive"))
    )
    (net (code "30") (name "GND") (class "Default")
      (node (ref "C1") (pin "2") (pinfunction "2_2") (pintype "passive"))
      (node (ref "C10") (pin "2") (pinfunction "2_2") (pintype "passive"))
      (node (ref "C11") (pin "+") (pinfunction "+_+") (pintype "passive"))
      (node (ref "C12") (pin "2") (pinfunction "2_2") (pintype "passive"))
      (node (ref "C13") (pin "2") (pinfunction "2_2") (pintype "passive"))
      (node (ref "C14") (pin "2") (pinfunction "2_2") (pintype "passive"))
      (node (ref "C15") (pin "2") (pinfunction "2_2") (pintype "passive"))
      (node (ref "C16") (pin "2") (pinfunction "2_2") (pintype "passive"))
      (node (ref "C17") (pin "-") (pinfunction "-_-") (pintype "passive"))
      (node (ref "C18") (pin "-") (pinfunction "-_-") (pintype "passive"))
      (node (ref "C19") (pin "2") (pinfunction "2_2") (pintype "passive"))
      (node (ref "C2") (pin "-") (pinfunction "-_-") (pintype "passive"))
      (node (ref "C20") (pin "2") (pinfunction "2_2") (pintype "passive"))
      (node (ref "C21") (pin "2") (pinfunction "2_2") (pintype "passive"))
      (node (ref "C25") (pin "2") (pinfunction "2_2") (pintype "passive"))
      (node (ref "C26") (pin "2") (pinfunction "2_2") (pintype "passive"))
      (node (ref "C3") (pin "2") (pinfunction "2_2") (pintype "passive"))
      (node (ref "C4") (pin "1") (pinfunction "1_1") (pintype "passive"))
      (node (ref "C46") (pin "2") (pinfunction "2_2") (pintype "passive"))
      (node (ref "C47") (pin "2") (pinfunction "2_2") (pintype "passive"))
      (node (ref "C5") (pin "2") (pinfunction "2_2") (pintype "passive"))
      (node (ref "C52") (pin "2") (pinfunction "2_2") (pintype "passive"))
      (node (ref "C6") (pin "1") (pinfunction "1_1") (pintype "passive"))
      (node (ref "C7") (pin "2") (pinfunction "2_2") (pintype "passive"))
      (node (ref "C8") (pin "-") (pinfunction "-_-") (pintype "passive"))
      (node (ref "C9") (pin "2") (pinfunction "2_2") (pintype "passive"))
      (node (ref "IC1") (pin "2") (pinfunction "GND_2") (pintype "passive"))
      (node (ref "IC2") (pin "12") (pinfunction "VSSA_12") (pintype "power_in"))
      (node (ref "IC2") (pin "18") (pinfunction "VSS_4_18") (pintype "power_in"))
      (node (ref "IC2") (pin "28") (pinfunction "PB2/BOOT1_28") (pintype "bidirectional"))
      (node (ref "IC2") (pin "60") (pinfunction "BOOT0_60") (pintype "bidirectional"))
      (node (ref "IC2") (pin "63") (pinfunction "VSS_3_63") (pintype "power_in"))
      (node (ref "IC3") (pin "2") (pinfunction "GND_2") (pintype "passive"))
      (node (ref "IC3") (pin "2@1") (pinfunction "GND_2@1") (pintype "passive"))
      (node (ref "IC4") (pin "13") (pinfunction "A0_13") (pintype "input"))
      (node (ref "IC4") (pin "14") (pinfunction "A1_14") (pintype "input"))
      (node (ref "IC4") (pin "15") (pinfunction "ENABLE_15") (pintype "input"))
      (node (ref "IC4") (pin "16") (pinfunction "LDAC_16") (pintype "input"))
      (node (ref "IC4") (pin "5") (pinfunction "VREFL_5") (pintype "bidirectional"))
      (node (ref "IC4") (pin "6") (pinfunction "GND_6") (pintype "power_in"))
      (node (ref "IC5") (pin "10") (pinfunction "+IN_10") (pintype "input"))
      (node (ref "IC5") (pin "11") (pinfunction "V-_11") (pintype "power_in"))
      (node (ref "IC5") (pin "12") (pinfunction "+IN_12") (pintype "input"))
      (node (ref "IC5") (pin "3") (pinfunction "+IN_3") (pintype "input"))
      (node (ref "IC5") (pin "5") (pinfunction "+IN_5") (pintype "input"))
      (node (ref "IC6") (pin "10") (pinfunction "+IN_10") (pintype "input"))
      (node (ref "IC6") (pin "11") (pinfunction "V-_11") (pintype "power_in"))
      (node (ref "IC6") (pin "12") (pinfunction "+IN_12") (pintype "input"))
      (node (ref "IC6") (pin "3") (pinfunction "+IN_3") (pintype "input"))
      (node (ref "IC6") (pin "5") (pinfunction "+IN_5") (pintype "input"))
      (node (ref "IC8") (pin "1") (pinfunction "C_1") (pintype "passive"))
      (node (ref "JP1") (pin "1") (pinfunction "1_1") (pintype "passive"))
      (node (ref "JP4") (pin "3") (pinfunction "3_3") (pintype "passive"))
      (node (ref "JP4") (pin "5") (pinfunction "5_5") (pintype "passive"))
      (node (ref "JP4") (pin "7") (pinfunction "7_7") (pintype "passive"))
      (node (ref "JP4") (pin "9") (pinfunction "9_9") (pintype "passive"))
      (node (ref "JP40") (pin "1") (pinfunction "1_1") (pintype "passive"))
      (node (ref "JP54") (pin "1") (pinfunction "1_1") (pintype "passive"))
      (node (ref "JP55") (pin "1") (pinfunction "1_1") (pintype "passive"))
      (node (ref "JP56") (pin "1") (pinfunction "1_1") (pintype "passive"))
      (node (ref "P1") (pin "3") (pinfunction "GND_3") (pintype "bidirectional"))
      (node (ref "P1") (pin "4") (pinfunction "GND_4") (pintype "bidirectional"))
      (node (ref "P1") (pin "5") (pinfunction "GND_5") (pintype "bidirectional"))
      (node (ref "P1") (pin "6") (pinfunction "GND_6") (pintype "bidirectional"))
      (node (ref "P1") (pin "7") (pinfunction "GND_7") (pintype "bidirectional"))
      (node (ref "P1") (pin "8") (pinfunction "GND_8") (pintype "bidirectional"))
      (node (ref "Q1") (pin "2") (pinfunction "LID1_2") (pintype "power_in"))
      (node (ref "Q1") (pin "4") (pinfunction "LID2_4") (pintype "power_in"))
    )
    (net (code "31") (name "LED_T_DV") (class "Default")
      (node (ref "IC2") (pin "29") (pinfunction "PB10/SPI2_SCK/I2S_SCK/I2C2_SCL/USART3_TX_29") (pintype "bidirectional"))
      (node (ref "JP75") (pin "1") (pinfunction "1_1") (pintype "passive"))
    )
    (net (code "32") (name "LED_T_MODE_G") (class "Default")
      (node (ref "IC2") (pin "33") (pinfunction "PB12/SPI2_NSS/I2S2_WS/I2C2_SMBA/USART3_CK/TIM1_BKIN_33") (pintype "bidirectional"))
      (node (ref "JP88") (pin "1") (pinfunction "1_1") (pintype "passive"))
    )
    (net (code "33") (name "LED_T_MODE_R") (class "Default")
      (node (ref "IC2") (pin "34") (pinfunction "PB13/SPI2_SCK/I2S2_SCK/USART3_CTS/TIM1_CH1N_34") (pintype "bidirectional"))
      (node (ref "JP87") (pin "1") (pinfunction "1_1") (pintype "passive"))
    )
    (net (code "34") (name "LED_T_RANGE_G") (class "Default")
      (node (ref "IC2") (pin "37") (pinfunction "PC6/I2S2_MCK_37") (pintype "bidirectional"))
      (node (ref "JP86") (pin "1") (pinfunction "1_1") (pintype "passive"))
    )
    (net (code "35") (name "LED_T_RANGE_R") (class "Default")
      (node (ref "IC2") (pin "38") (pinfunction "PC7/I2S3_MCK_38") (pintype "bidirectional"))
      (node (ref "JP85") (pin "1") (pinfunction "1_1") (pintype "passive"))
    )
    (net (code "36") (name "LED_X_DV") (class "Default")
      (node (ref "IC2") (pin "62") (pinfunction "PB9/SPI2_NSS/I2S2_WS/I2C1_SDA/TIM4_CH4_62") (pintype "bidirectional"))
      (node (ref "JP77") (pin "1") (pinfunction "1_1") (pintype "passive"))
    )
    (net (code "37") (name "LED_X_EXT_G") (class "Default")
      (node (ref "IC2") (pin "55") (pinfunction "PB3/JTDO/SPI3_SCK/I2S3_SCK_55") (pintype "bidirectional"))
      (node (ref "JP4") (pin "6") (pinfunction "6_6") (pintype "passive"))
      (node (ref "JP84") (pin "1") (pinfunction "1_1") (pintype "passive"))
    )
    (net (code "38") (name "LED_X_MODE_G") (class "Default")
      (node (ref "IC2") (pin "59") (pinfunction "PB7/I2C1_SDA/TIM4_CH2/USART1_RX_59") (pintype "bidirectional"))
      (node (ref "JP90") (pin "1") (pinfunction "1_1") (pintype "passive"))
    )
    (net (code "39") (name "LED_X_MODE_R") (class "Default")
      (node (ref "IC2") (pin "61") (pinfunction "PB8/TIM4_CH3/I2C1_SCL_61") (pintype "bidirectional"))
      (node (ref "JP89") (pin "1") (pinfunction "1_1") (pintype "passive"))
    )
    (net (code "40") (name "LED_X_RANGE_G") (class "Default")
      (node (ref "IC2") (pin "57") (pinfunction "PB5/I2C1_SMBA/SPI1_MOSI/SPI3_MOSI/I2S3_SD_57") (pintype "bidirectional"))
      (node (ref "JP92") (pin "1") (pinfunction "1_1") (pintype "passive"))
    )
    (net (code "41") (name "LED_X_RANGE_R") (class "Default")
      (node (ref "IC2") (pin "56") (pinfunction "PB4/NJTRST/SPI3_MISO/SPI1_MISO_56") (pintype "bidirectional"))
      (node (ref "JP91") (pin "1") (pinfunction "1_1") (pintype "passive"))
    )
    (net (code "42") (name "L_DV_CV") (class "Default")
      (node (ref "C33") (pin "1") (pinfunction "1_1") (pintype "passive"))
      (node (ref "IC6") (pin "9") (pinfunction "-IN_9") (pintype "input"))
      (node (ref "JP63") (pin "1") (pinfunction "1_1") (pintype "passive"))
      (node (ref "R31") (pin "1") (pinfunction "1_1") (pintype "passive"))
      (node (ref "R42") (pin "2") (pinfunction "2_2") (pintype "passive"))
    )
    (net (code "43") (name "L_T_BIAS_CV") (class "Default")
      (node (ref "C40") (pin "1") (pinfunction "1_1") (pintype "passive"))
      (node (ref "IC5") (pin "6") (pinfunction "-IN_6") (pintype "input"))
      (node (ref "JP49") (pin "1") (pinfunction "1_1") (pintype "passive"))
      (node (ref "R57") (pin "2") (pinfunction "2_2") (pintype "passive"))
      (node (ref "R70") (pin "1") (pinfunction "1_1") (pintype "passive"))
    )
    (net (code "44") (name "L_T_JITTER_CV") (class "Default")
      (node (ref "C42") (pin "1") (pinfunction "1_1") (pintype "passive"))
      (node (ref "IC5") (pin "2") (pinfunction "-IN_2") (pintype "input"))
      (node (ref "JP52") (pin "1") (pinfunction "1_1") (pintype "passive"))
      (node (ref "R59") (pin "2") (pinfunction "2_2") (pintype "passive"))
      (node (ref "R72") (pin "1") (pinfunction "1_1") (pintype "passive"))
    )
    (net (code "45") (name "L_T_RATE_CV") (class "Default")
      (node (ref "C41") (pin "1") (pinfunction "1_1") (pintype "passive"))
      (node (ref "IC5") (pin "9") (pinfunction "-IN_9") (pintype "input"))
      (node (ref "JP50") (pin "1") (pinfunction "1_1") (pintype "passive"))
      (node (ref "R58") (pin "2") (pinfunction "2_2") (pintype "passive"))
      (node (ref "R71") (pin "1") (pinfunction "1_1") (pintype "passive"))
    )
    (net (code "46") (name "L_X_BIAS_CV") (class "Default")
      (node (ref "C30") (pin "1") (pinfunction "1_1") (pintype "passive"))
      (node (ref "IC6") (pin "2") (pinfunction "-IN_2") (pintype "input"))
      (node (ref "JP61") (pin "1") (pinfunction "1_1") (pintype "passive"))
      (node (ref "R30") (pin "1") (pinfunction "1_1") (pintype "passive"))
      (node (ref "R39") (pin "2") (pinfunction "2_2") (pintype "passive"))
    )
    (net (code "47") (name "L_X_SPREAD_CV") (class "Default")
      (node (ref "C31") (pin "1") (pinfunction "1_1") (pintype "passive"))
      (node (ref "IC6") (pin "13") (pinfunction "-IN_13") (pintype "input"))
      (node (ref "JP59") (pin "1") (pinfunction "1_1") (pintype "passive"))
      (node (ref "R28") (pin "1") (pinfunction "1_1") (pintype "passive"))
      (node (ref "R40") (pin "2") (pinfunction "2_2") (pintype "passive"))
    )
    (net (code "48") (name "L_X_STEPS_CV") (class "Default")
      (node (ref "C32") (pin "1") (pinfunction "1_1") (pintype "passive"))
      (node (ref "IC6") (pin "6") (pinfunction "-IN_6") (pintype "input"))
      (node (ref "JP57") (pin "1") (pinfunction "1_1") (pintype "passive"))
      (node (ref "R29") (pin "1") (pinfunction "1_1") (pintype "passive"))
      (node (ref "R41") (pin "2") (pinfunction "2_2") (pintype "passive"))
    )
    (net (code "49") (name "NORMALIZATION_PROBE") (class "Default")
      (node (ref "IC2") (pin "39") (pinfunction "PC8_39") (pintype "bidirectional"))
      (node (ref "JP66") (pin "1") (pinfunction "1_1") (pintype "passive"))
    )
    (net (code "50") (name "Net-(C6-Pad2)") (class "Default")
      (node (ref "C6") (pin "2") (pinfunction "2_2") (pintype "passive"))
      (node (ref "Q1") (pin "1") (pinfunction "1_1") (pintype "passive"))
      (node (ref "R7") (pin "2") (pinfunction "2_2") (pintype "passive"))
    )
    (net (code "51") (name "Net-(D1-Pad+)") (class "Default")
      (node (ref "D1") (pin "+") (pinfunction "+_+") (pintype "passive"))
      (node (ref "P1") (pin "10") (pinfunction "+12V_10") (pintype "bidirectional"))
      (node (ref "P1") (pin "9") (pinfunction "+12V_9") (pintype "bidirectional"))
    )
    (net (code "52") (name "Net-(D2-Pad-)") (class "Default")
      (node (ref "D2") (pin "-") (pinfunction "-_-") (pintype "passive"))
      (node (ref "P1") (pin "1") (pinfunction "-12V_1") (pintype "bidirectional"))
      (node (ref "P1") (pin "2") (pinfunction "-12V_2") (pintype "bidirectional"))
    )
    (net (code "53") (name "Net-(F1-P$2)") (class "Default")
      (node (ref "C5") (pin "1") (pinfunction "1_1") (pintype "passive"))
      (node (ref "D1") (pin "-") (pinfunction "-_-") (pintype "passive"))
      (node (ref "F1") (pin "2") (pinfunction "P$2_2") (pintype "bidirectional"))
      (node (ref "F3") (pin "2") (pinfunction "P$2_2") (pintype "bidirectional"))
      (node (ref "L1") (pin "1") (pinfunction "1_1") (pintype "passive"))
    )
    (net (code "54") (name "Net-(F2-P$2)") (class "Default")
      (node (ref "D2") (pin "+") (pinfunction "+_+") (pintype "passive"))
      (node (ref "F2") (pin "2") (pinfunction "P$2_2") (pintype "bidirectional"))
    )
    (net (code "55") (name "Net-(F3-P$1)") (class "Default")
      (node (ref "C14") (pin "1") (pinfunction "1_1") (pintype "passive"))
      (node (ref "F3") (pin "1") (pinfunction "P$1_1") (pintype "bidirectional"))
      (node (ref "IC3") (pin "3") (pinfunction "VI_3") (pintype "input"))
    )
    (net (code "56") (name "Net-(IC1-VI)") (class "Default")
      (node (ref "C3") (pin "1") (pinfunction "1_1") (pintype "passive"))
      (node (ref "IC1") (pin "1") (pinfunction "VI_1") (pintype "input"))
      (node (ref "L1") (pin "2") (pinfunction "2_2") (pintype "passive"))
    )
    (net (code "57") (name "Net-(IC2-PD0{slash}OSC_IN)") (class "Default")
      (node (ref "IC2") (pin "5") (pinfunction "PD0/OSC_IN_5") (pintype "bidirectional"))
      (node (ref "R8") (pin "1") (pinfunction "1_1") (pintype "passive"))
    )
    (net (code "58") (name "Net-(IC2-PD1{slash}OSC_OUT)") (class "Default")
      (node (ref "IC2") (pin "6") (pinfunction "PD1/OSC_OUT_6") (pintype "bidirectional"))
      (node (ref "R7") (pin "1") (pinfunction "1_1") (pintype "passive"))
    )
    (net (code "59") (name "Net-(IC2-VCAP_1)") (class "Default")
      (node (ref "C15") (pin "1") (pinfunction "1_1") (pintype "passive"))
      (node (ref "IC2") (pin "31") (pinfunction "VCAP_1_31") (pintype "power_in"))
    )
    (net (code "60") (name "Net-(IC2-VCAP_2)") (class "Default")
      (node (ref "C20") (pin "1") (pinfunction "1_1") (pintype "passive"))
      (node (ref "IC2") (pin "47") (pinfunction "VCAP_2_47") (pintype "power_in"))
    )
    (net (code "61") (name "Net-(JP2-Pad1)") (class "Default")
      (node (ref "JP2") (pin "1") (pinfunction "1_1") (pintype "passive"))
      (node (ref "R3") (pin "1") (pinfunction "1_1") (pintype "passive"))
    )
    (net (code "62") (name "Net-(JP2-Pad2)") (class "Default")
      (node (ref "JP2") (pin "2") (pinfunction "2_2") (pintype "passive"))
      (node (ref "R2") (pin "1") (pinfunction "1_1") (pintype "passive"))
    )
    (net (code "63") (name "Net-(JP3-Pad2)") (class "Default")
      (node (ref "JP3") (pin "2") (pinfunction "2_2") (pintype "passive"))
      (node (ref "JP53") (pin "1") (pinfunction "1_1") (pintype "passive"))
    )
    (net (code "64") (name "Net-(Q1B-2)") (class "Default")
      (node (ref "C4") (pin "2") (pinfunction "2_2") (pintype "passive"))
      (node (ref "Q1") (pin "3") (pinfunction "2_3") (pintype "passive"))
      (node (ref "R8") (pin "2") (pinfunction "2_2") (pintype "passive"))
    )
    (net (code "65") (name "RESET") (class "Default")
      (node (ref "C7") (pin "1") (pinfunction "1_1") (pintype "passive"))
      (node (ref "IC2") (pin "7") (pinfunction "NRST_7") (pintype "bidirectional"))
      (node (ref "JP1") (pin "4") (pinfunction "4_4") (pintype "passive"))
      (node (ref "JP4") (pin "10") (pinfunction "10_10") (pintype "passive"))
      (node (ref "R6") (pin "1") (pinfunction "1_1") (pintype "passive"))
    )
    (net (code "66") (name "RX") (class "Default")
      (node (ref "IC2") (pin "43") (pinfunction "PA10/USART1_RX/TIM1_CH3_43") (pintype "bidirectional"))
      (node (ref "R3") (pin "2") (pinfunction "2_2") (pintype "passive"))
    )
    (net (code "67") (name "SWCLK") (class "Default")
      (node (ref "IC2") (pin "49") (pinfunction "PA14/JTCK-SWCLK_49") (pintype "bidirectional"))
      (node (ref "JP1") (pin "3") (pinfunction "3_3") (pintype "passive"))
      (node (ref "JP4") (pin "4") (pinfunction "4_4") (pintype "passive"))
    )
    (net (code "68") (name "SWDIO") (class "Default")
      (node (ref "IC2") (pin "46") (pinfunction "PA13/JTMS-SWDAT_46") (pintype "bidirectional"))
      (node (ref "JP1") (pin "2") (pinfunction "2_2") (pintype "passive"))
      (node (ref "JP4") (pin "2") (pinfunction "2_2") (pintype "passive"))
    )
    (net (code "69") (name "SW_T_DV") (class "Default")
      (node (ref "IC2") (pin "30") (pinfunction "PB11/I2C2_SDA/USART3_RX_30") (pintype "bidirectional"))
      (node (ref "JP76") (pin "1") (pinfunction "1_1") (pintype "passive"))
    )
    (net (code "70") (name "SW_T_MODE") (class "Default")
      (node (ref "IC2") (pin "35") (pinfunction "PB14/SPI2_MISO/USART3_RTS/TIM1_CH2N_35") (pintype "bidirectional"))
      (node (ref "JP81") (pin "1") (pinfunction "1_1") (pintype "passive"))
    )
    (net (code "71") (name "SW_T_RANGE") (class "Default")
      (node (ref "IC2") (pin "36") (pinfunction "PB15/SPI2_MOSI/I2S2_SD/TIM1_CH3N_36") (pintype "bidirectional"))
      (node (ref "JP80") (pin "1") (pinfunction "1_1") (pintype "passive"))
    )
    (net (code "72") (name "SW_X_DV") (class "Default")
      (node (ref "IC2") (pin "4") (pinfunction "PC15/OSC_OUT_4") (pintype "bidirectional"))
      (node (ref "JP78") (pin "1") (pinfunction "1_1") (pintype "passive"))
    )
    (net (code "73") (name "SW_X_EXT") (class "Default")
      (node (ref "IC2") (pin "54") (pinfunction "PD2/TIM3-ETR_54") (pintype "bidirectional"))
      (node (ref "JP79") (pin "1") (pinfunction "1_1") (pintype "passive"))
    )
    (net (code "74") (name "SW_X_MODE") (class "Default")
      (node (ref "IC2") (pin "2") (pinfunction "PC13-TAMPER-RTC_2") (pintype "bidirectional"))
      (node (ref "JP82") (pin "1") (pinfunction "1_1") (pintype "passive"))
    )
    (net (code "75") (name "SW_X_RANGE") (class "Default")
      (node (ref "IC2") (pin "58") (pinfunction "PB6/I2C1_SCL/TIM4_CH1/USART1_TX_58") (pintype "bidirectional"))
      (node (ref "JP83") (pin "1") (pinfunction "1_1") (pintype "passive"))
    )
    (net (code "76") (name "TX") (class "Default")
      (node (ref "IC2") (pin "42") (pinfunction "PA9/USART1_TX/TIM1_CH2_42") (pintype "bidirectional"))
      (node (ref "R2") (pin "2") (pinfunction "2_2") (pintype "passive"))
    )
    (net (code "77") (name "T_CLOCK") (class "Default")
      (node (ref "IC2") (pin "40") (pinfunction "PC9/I2S2_CKIN/I2S3_CKIN_40") (pintype "bidirectional"))
      (node (ref "JP64") (pin "1") (pinfunction "1_1") (pintype "passive"))
    )
    (net (code "78") (name "VCC") (class "Default")
      (node (ref "C2") (pin "+") (pinfunction "+_+") (pintype "passive"))
      (node (ref "F1") (pin "1") (pinfunction "P$1_1") (pintype "bidirectional"))
      (node (ref "JP3") (pin "1") (pinfunction "1_1") (pintype "passive"))
      (node (ref "JP38") (pin "1") (pinfunction "1_1") (pintype "passive"))
    )
    (net (code "79") (name "VEE") (class "Default")
      (node (ref "C11") (pin "-") (pinfunction "-_-") (pintype "passive"))
      (node (ref "F2") (pin "1") (pinfunction "P$1_1") (pintype "bidirectional"))
      (node (ref "JP39") (pin "1") (pinfunction "1_1") (pintype "passive"))
      (node (ref "R68") (pin "1") (pinfunction "1_1") (pintype "passive"))
    )
    (net (code "80") (name "VREF") (class "Default")
      (node (ref "C25") (pin "1") (pinfunction "1_1") (pintype "passive"))
      (node (ref "IC4") (pin "3") (pinfunction "VREFH_3") (pintype "bidirectional"))
      (node (ref "JP100") (pin "1") (pinfunction "1_1") (pintype "passive"))
    )
    (net (code "81") (name "X_CLOCK") (class "Default")
      (node (ref "IC2") (pin "41") (pinfunction "PA8/USART1_CK/TIM1_CH1/MCO_41") (pintype "bidirectional"))
      (node (ref "JP65") (pin "1") (pinfunction "1_1") (pintype "passive"))
    )
    (net (code "82") (name "unconnected-(IC2-PC14{slash}OSC32_IN-Pad3)") (class "Default")
      (node (ref "IC2") (pin "3") (pinfunction "PC14/OSC32_IN_3") (pintype "bidirectional"))
    )
    (net (code "83") (name "unconnected-(JP3-Pad3)") (class "Default")
      (node (ref "JP3") (pin "3") (pinfunction "3_3") (pintype "passive"))
    )
  )
)
